# 3_6_2--esp32S3.net
KiCad netlist of a schematic drawn in EasyEDA Pro
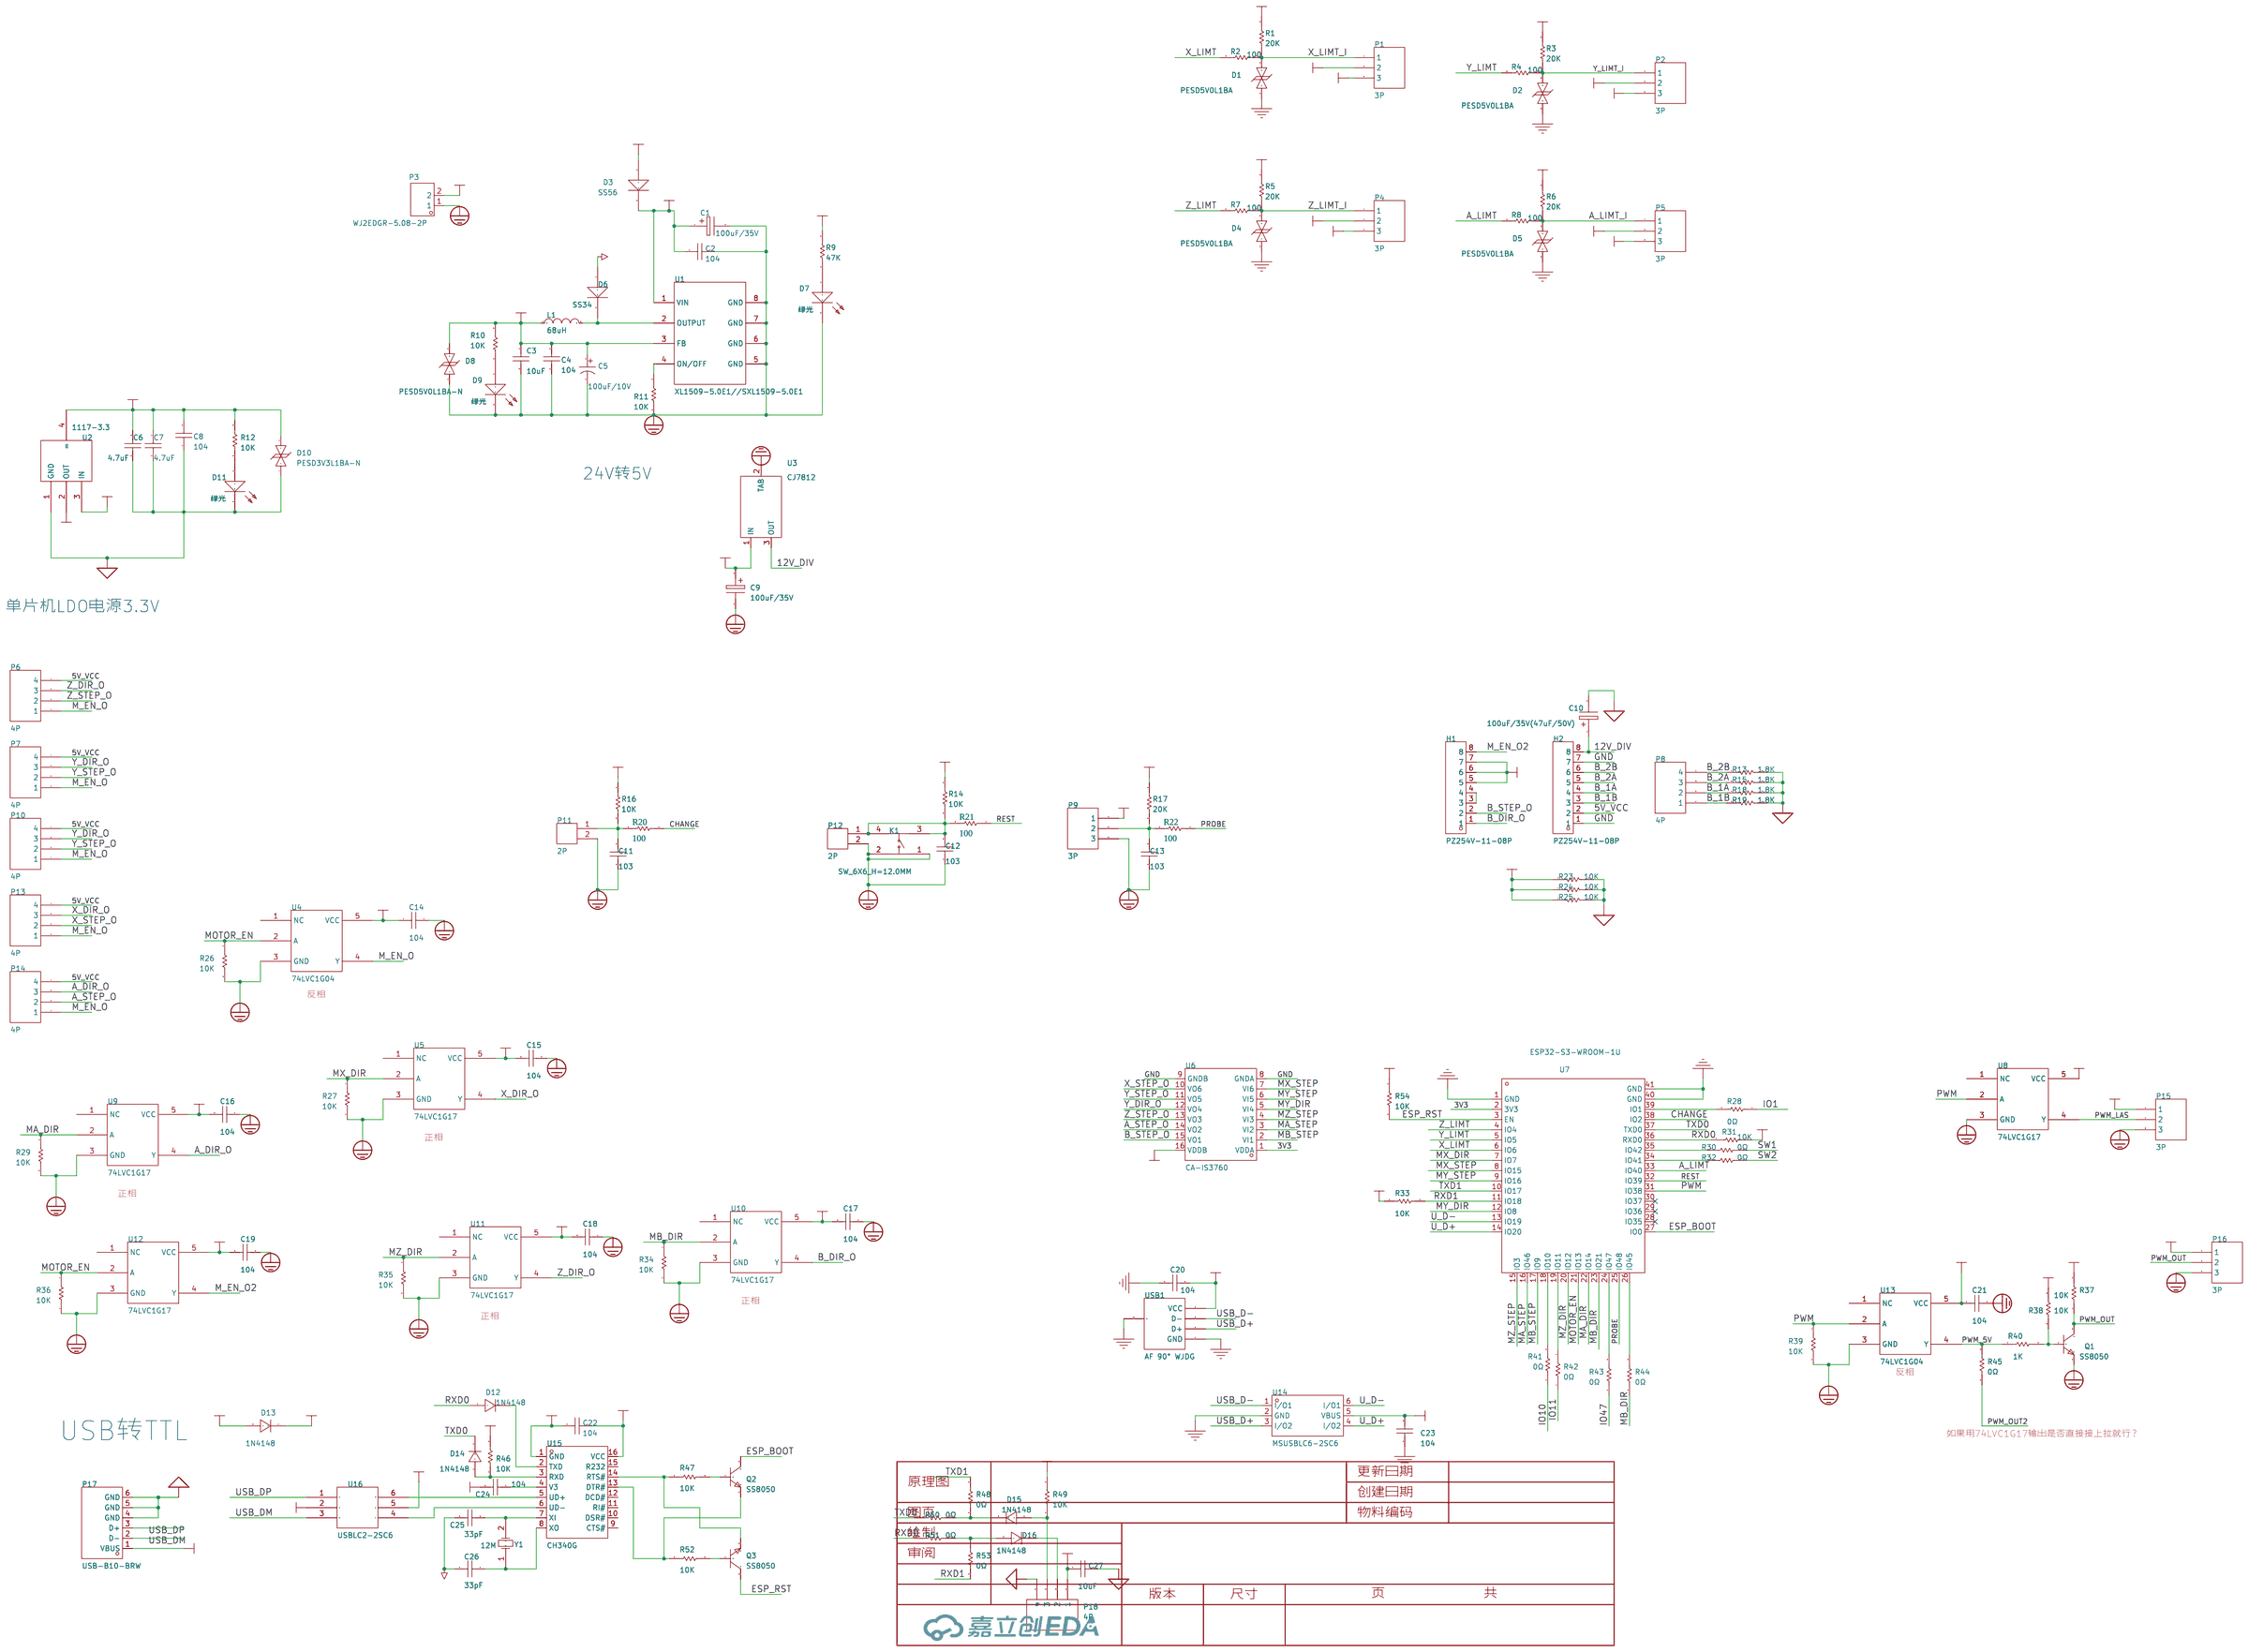
[diagram p0: schematic sheet]

(export (version "E")
  (design (tool "Eeschema 10.0.6"))
  (components
    (comp (ref "C1")
      (value "100uF/35V")
      (footprint "easyedapro:电解电容贴片10x10")
      (libsource (lib "easyedapro") (part "ELECTRO1"))
    )
    (comp (ref "C2")
      (value "104")
      (footprint "easyedapro:0603C")
      (description "Capacitor (Semiconductor SIM Model)")
      (libsource (lib "easyedapro") (part "Cap Semi"))
    )
    (comp (ref "C3") (value "10uF") (libsource (lib "") (part "CAP_1")))
    (comp (ref "C4")
      (value "104")
      (footprint "easyedapro:0603C")
      (description "Capacitor (Semiconductor SIM Model)")
      (libsource (lib "easyedapro") (part "Cap Semi"))
    )
    (comp (ref "C5")
      (value "100uF/10V")
      (footprint "easyedapro:CAP-SMD_BD5.0-L5.3-W5.3-RD")
      (fields (field (name "Manufacturer Part") "CS1A101M-CRD54") (field (name "Manufacturer") "ST(先科)"))
      (libsource (lib "easyedapro") (part "CS1A101M-CRD54"))
    )
    (comp (ref "C6") (value "4.7uF") (libsource (lib "") (part "CAP_1")))
    (comp (ref "C7") (value "4.7uF") (libsource (lib "") (part "CAP_1")))
    (comp (ref "C8")
      (value "104")
      (footprint "easyedapro:0603C")
      (description "Capacitor (Semiconductor SIM Model)")
      (libsource (lib "easyedapro") (part "Cap Semi"))
    )
    (comp (ref "C9")
      (value "100uF/35V")
      (footprint "easyedapro:电解电容贴片10x10")
      (libsource (lib "easyedapro") (part "ELECTRO1"))
    )
    (comp (ref "C10")
      (value "100uF/35V(47uF/50V)")
      (footprint "easyedapro:电解电容贴片10x10")
      (libsource (lib "easyedapro") (part "ELECTRO1"))
    )
    (comp (ref "C11") (value "103") (footprint "easyedapro:11") (libsource (lib "easyedapro") (part "CAP")))
    (comp (ref "C12") (value "103") (footprint "easyedapro:11") (libsource (lib "easyedapro") (part "CAP")))
    (comp (ref "C13") (value "103") (footprint "easyedapro:11") (libsource (lib "easyedapro") (part "CAP")))
    (comp (ref "C14")
      (value "104")
      (footprint "easyedapro:0603C")
      (description "Capacitor (Semiconductor SIM Model)")
      (libsource (lib "easyedapro") (part "Cap Semi"))
    )
    (comp (ref "C15")
      (value "104")
      (footprint "easyedapro:0603C")
      (description "Capacitor (Semiconductor SIM Model)")
      (libsource (lib "easyedapro") (part "Cap Semi"))
    )
    (comp (ref "C16")
      (value "104")
      (footprint "easyedapro:0603C")
      (description "Capacitor (Semiconductor SIM Model)")
      (libsource (lib "easyedapro") (part "Cap Semi"))
    )
    (comp (ref "C17")
      (value "104")
      (footprint "easyedapro:0603C")
      (description "Capacitor (Semiconductor SIM Model)")
      (libsource (lib "easyedapro") (part "Cap Semi"))
    )
    (comp (ref "C18")
      (value "104")
      (footprint "easyedapro:0603C")
      (description "Capacitor (Semiconductor SIM Model)")
      (libsource (lib "easyedapro") (part "Cap Semi"))
    )
    (comp (ref "C19")
      (value "104")
      (footprint "easyedapro:0603C")
      (description "Capacitor (Semiconductor SIM Model)")
      (libsource (lib "easyedapro") (part "Cap Semi"))
    )
    (comp (ref "C20")
      (value "104")
      (footprint "easyedapro:0603C")
      (description "Capacitor (Semiconductor SIM Model)")
      (libsource (lib "easyedapro") (part "Cap Semi"))
    )
    (comp (ref "C21")
      (value "104")
      (footprint "easyedapro:0603C")
      (description "Capacitor (Semiconductor SIM Model)")
      (libsource (lib "easyedapro") (part "Cap Semi"))
    )
    (comp (ref "C22")
      (value "104")
      (footprint "easyedapro:0603C")
      (description "Capacitor (Semiconductor SIM Model)")
      (libsource (lib "easyedapro") (part "Cap Semi"))
    )
    (comp (ref "C23")
      (value "104")
      (footprint "easyedapro:0603C")
      (description "Capacitor (Semiconductor SIM Model)")
      (libsource (lib "easyedapro") (part "Cap Semi"))
    )
    (comp (ref "C24")
      (value "104")
      (footprint "easyedapro:0603C")
      (description "Capacitor (Semiconductor SIM Model)")
      (libsource (lib "easyedapro") (part "Cap Semi"))
    )
    (comp (ref "C25")
      (value "18pF")
      (footprint "easyedapro:0603C")
      (description "Capacitor (Semiconductor SIM Model)")
      (libsource (lib "easyedapro") (part "Cap Semi"))
    )
    (comp (ref "C26")
      (value "18pF")
      (footprint "easyedapro:0603C")
      (description "Capacitor (Semiconductor SIM Model)")
      (libsource (lib "easyedapro") (part "Cap Semi"))
    )
    (comp (ref "C27") (value "10uF") (libsource (lib "") (part "CAP_1")))
    (comp (ref "D1")
      (value "PESD5V0L1BA")
      (footprint "easyedapro:SOD-523_L1.2-W0.8-LS1.6-BI")
      (description "极性:Bidirectional;反向关断电压（典型值）:5V (Max);击穿电压（最小值）:6V;箝位电压:15V;峰值脉冲电流（10/1000us）:5A (8/20us);")
      (fields (field (name "Manufacturer") "BORN伯恩半导体"))
      (libsource (lib "easyedapro") (part "PESD5V0S1BBN"))
    )
    (comp (ref "D2")
      (value "PESD5V0L1BA")
      (footprint "easyedapro:SOD-523_L1.2-W0.8-LS1.6-BI")
      (description "极性:Bidirectional;反向关断电压（典型值）:5V (Max);击穿电压（最小值）:6V;箝位电压:15V;峰值脉冲电流（10/1000us）:5A (8/20us);")
      (fields (field (name "Manufacturer") "BORN伯恩半导体"))
      (libsource (lib "easyedapro") (part "PESD5V0S1BBN"))
    )
    (comp (ref "D3") (value "SS56") (footprint "easyedapro:SMA") (libsource (lib "") (part "1N4148_1")))
    (comp (ref "D4")
      (value "PESD5V0L1BA")
      (footprint "easyedapro:SOD-523_L1.2-W0.8-LS1.6-BI")
      (description "极性:Bidirectional;反向关断电压（典型值）:5V (Max);击穿电压（最小值）:6V;箝位电压:15V;峰值脉冲电流（10/1000us）:5A (8/20us);")
      (fields (field (name "Manufacturer") "BORN伯恩半导体"))
      (libsource (lib "easyedapro") (part "PESD5V0S1BBN"))
    )
    (comp (ref "D5")
      (value "PESD5V0L1BA")
      (footprint "easyedapro:SOD-523_L1.2-W0.8-LS1.6-BI")
      (description "极性:Bidirectional;反向关断电压（典型值）:5V (Max);击穿电压（最小值）:6V;箝位电压:15V;峰值脉冲电流（10/1000us）:5A (8/20us);")
      (fields (field (name "Manufacturer") "BORN伯恩半导体"))
      (libsource (lib "easyedapro") (part "PESD5V0S1BBN"))
    )
    (comp (ref "D6") (value "SS34") (libsource (lib "easyedapro") (part "1N4148")))
    (comp (ref "D7")
      (value "绿光")
      (footprint "easyedapro:0603LED")
      (libsource (lib "easyedapro") (part "LED"))
    )
    (comp (ref "D8")
      (value "PESD5V0L1BA-N")
      (footprint "easyedapro:SOD-523_L1.2-W0.8-LS1.6-BI")
      (description "极性:Bidirectional;反向关断电压（典型值）:5V (Max);击穿电压（最小值）:6V;箝位电压:15V;峰值脉冲电流（10/1000us）:5A (8/20us);")
      (fields (field (name "Manufacturer") "BORN伯恩半导体"))
      (libsource (lib "easyedapro") (part "PESD5V0S1BBN"))
    )
    (comp (ref "D9")
      (value "绿光")
      (footprint "easyedapro:0603LED")
      (libsource (lib "easyedapro") (part "LED"))
    )
    (comp (ref "D10")
      (value "PESD3V3L1BA-N")
      (footprint "easyedapro:SOD-523_L1.2-W0.8-LS1.6-BI")
      (description "极性:Bidirectional;反向关断电压（典型值）:5V (Max);击穿电压（最小值）:6V;箝位电压:15V;峰值脉冲电流（10/1000us）:5A (8/20us);")
      (fields (field (name "Manufacturer") "BORN伯恩半导体"))
      (libsource (lib "easyedapro") (part "PESD5V0S1BBN"))
    )
    (comp (ref "D11")
      (value "绿光")
      (footprint "easyedapro:0603LED")
      (libsource (lib "easyedapro") (part "LED"))
    )
    (comp (ref "D12")
      (value "1N4148")
      (footprint "easyedapro:SOD-123_L2.8-W1.8-LS3.7-RD")
      (fields (field (name "Manufacturer") "MCC(美微科)"))
      (libsource (lib "easyedapro") (part "1N4148W-TP"))
    )
    (comp (ref "D13")
      (value "1N4148")
      (footprint "easyedapro:SOD-123_L2.8-W1.8-LS3.7-RD")
      (fields (field (name "Manufacturer") "MCC(美微科)"))
      (libsource (lib "easyedapro") (part "1N4148W-TP"))
    )
    (comp (ref "D14")
      (value "1N4148")
      (footprint "easyedapro:SOD-123_L2.8-W1.8-LS3.7-RD")
      (fields (field (name "Manufacturer") "MCC(美微科)"))
      (libsource (lib "easyedapro") (part "1N4148W-TP"))
    )
    (comp (ref "D15")
      (value "1N4148")
      (footprint "easyedapro:SOD-123_L2.8-W1.8-LS3.7-RD")
      (fields (field (name "Manufacturer") "MCC(美微科)"))
      (libsource (lib "easyedapro") (part "1N4148W-TP"))
    )
    (comp (ref "D16")
      (value "1N4148")
      (footprint "easyedapro:SOD-123_L2.8-W1.8-LS3.7-RD")
      (fields (field (name "Manufacturer") "MCC(美微科)"))
      (libsource (lib "easyedapro") (part "1N4148W-TP"))
    )
    (comp (ref "H1")
      (value "PZ254V-11-08P")
      (footprint "easyedapro:HDR-TH_8P-P2.54-V-M")
      (fields (field (name "Manufacturer") "XFCN(兴飞)"))
      (libsource (lib "easyedapro") (part "PZ254V-11-08P"))
    )
    (comp (ref "H2")
      (value "PZ254V-11-08P")
      (footprint "easyedapro:HDR-TH_8P-P2.54-V-M")
      (fields (field (name "Manufacturer") "XFCN(兴飞)"))
      (libsource (lib "easyedapro") (part "PZ254V-11-08P"))
    )
    (comp (ref "K1")
      (value "SW_6X6_H=12.0MM")
      (footprint "easyedapro:KEY-SMD_4P-L6.0-W6.0-P4.50-LS9.0")
      (libsource (lib "easyedapro") (part "SW_6X6_H=12.0MM"))
    )
    (comp (ref "L1")
      (value "68uH")
      (footprint "easyedapro:IND-SMD_L7.0-W7.0_SMDRI74-330MT")
      (description "电感值:33uH;精度:±20%;额定电流:960mA;饱和电流(Isat):1.8A;类型:屏蔽电感;")
      (fields (field (name "Manufacturer Part") "SMDRI74-330MT") (field (name "Manufacturer") "SXN(顺翔诺)"))
      (libsource (lib "easyedapro") (part "SMDRI74-330MT"))
    )
    (comp (ref "P1")
      (value "3P")
      (footprint "easyedapro:HDR1X3_CON")
      (libsource (lib "easyedapro") (part "3P"))
    )
    (comp (ref "P2")
      (value "3P")
      (footprint "easyedapro:HDR1X3_CON")
      (libsource (lib "easyedapro") (part "3P"))
    )
    (comp (ref "P3")
      (value "WJ2EDGR-5.08-2P")
      (footprint "easyedapro:CONN-TH_WJ2EDGR-5.08-2P")
      (description "每排PIN数:2;安装方式:弯针;排数:1;间距:5.08mm;连接器类型:板端/插座-开口;")
      (fields (field (name "Manufacturer") "KANGNEX(康奈克斯电气)"))
      (libsource (lib "easyedapro") (part "WJ2EDGR-5.08-2P"))
    )
    (comp (ref "P4")
      (value "3P")
      (footprint "easyedapro:HDR1X3_CON")
      (libsource (lib "easyedapro") (part "3P"))
    )
    (comp (ref "P5")
      (value "3P")
      (footprint "easyedapro:HDR1X3_CON")
      (libsource (lib "easyedapro") (part "3P"))
    )
    (comp (ref "P6")
      (value "4P")
      (footprint "easyedapro:HDR1X4_CON")
      (libsource (lib "easyedapro") (part "4P"))
    )
    (comp (ref "P7")
      (value "4P")
      (footprint "easyedapro:HDR1X4_CON")
      (libsource (lib "easyedapro") (part "4P"))
    )
    (comp (ref "P8")
      (value "4P")
      (footprint "easyedapro:HDR1X4_CON")
      (libsource (lib "easyedapro") (part "4P"))
    )
    (comp (ref "P9")
      (value "3P")
      (footprint "easyedapro:HDR1X3_CON")
      (libsource (lib "easyedapro") (part "3P"))
    )
    (comp (ref "P10")
      (value "4P")
      (footprint "easyedapro:HDR1X4_CON")
      (libsource (lib "easyedapro") (part "4P"))
    )
    (comp (ref "P11") (value "2P") (libsource (lib "easyedapro") (part "2P")))
    (comp (ref "P12") (value "2P") (libsource (lib "easyedapro") (part "2P")))
    (comp (ref "P13")
      (value "4P")
      (footprint "easyedapro:HDR1X4_CON")
      (libsource (lib "easyedapro") (part "4P"))
    )
    (comp (ref "P14")
      (value "4P")
      (footprint "easyedapro:HDR1X4_CON")
      (libsource (lib "easyedapro") (part "4P"))
    )
    (comp (ref "P15")
      (value "3P")
      (footprint "easyedapro:HDR1X3_CON")
      (libsource (lib "easyedapro") (part "3P"))
    )
    (comp (ref "P16")
      (value "3P")
      (footprint "easyedapro:HDR1X3_CON")
      (libsource (lib "easyedapro") (part "3P"))
    )
    (comp (ref "P17")
      (value "USB-B10-BRW")
      (footprint "easyedapro:USB-B-TH_USB-B10-BRW")
      (fields (field (name "Manufacturer") "XUNPU(讯普)"))
      (libsource (lib "easyedapro") (part "USB-B10-BRW"))
    )
    (comp (ref "P18")
      (value "4P")
      (footprint "easyedapro:HDR1X4_CON")
      (libsource (lib "easyedapro") (part "4P"))
    )
    (comp (ref "Q1")
      (value "SS8050")
      (footprint "easyedapro:SOT-23-3_L2.9-W1.3-P1.90-LS2.4-BR")
      (fields (field (name "Manufacturer") "CJ（江苏长电/长晶）"))
      (libsource (lib "easyedapro") (part "SS8050_C2150"))
    )
    (comp (ref "Q2")
      (value "SS8050")
      (footprint "easyedapro:SOT-23-3_L2.9-W1.3-P1.90-LS2.4-BR")
      (fields (field (name "Manufacturer") "Doeshare(德芯)"))
      (libsource (lib "easyedapro") (part "SS8050_C2931717"))
    )
    (comp (ref "Q3")
      (value "SS8050")
      (footprint "easyedapro:SOT-23-3_L2.9-W1.3-P1.90-LS2.4-BR")
      (fields (field (name "Manufacturer") "Doeshare(德芯)"))
      (libsource (lib "easyedapro") (part "SS8050_C2931717"))
    )
    (comp (ref "R1")
      (value "20K")
      (footprint "easyedapro:10")
      (description "Resistor")
      (libsource (lib "") (part "RES_1"))
    )
    (comp (ref "R2")
      (value "100")
      (footprint "easyedapro:10")
      (description "Resistor")
      (libsource (lib "") (part "RES_1"))
    )
    (comp (ref "R3")
      (value "20K")
      (footprint "easyedapro:10")
      (description "Resistor")
      (libsource (lib "") (part "RES_1"))
    )
    (comp (ref "R4")
      (value "100")
      (footprint "easyedapro:10")
      (description "Resistor")
      (libsource (lib "") (part "RES_1"))
    )
    (comp (ref "R5")
      (value "20K")
      (footprint "easyedapro:10")
      (description "Resistor")
      (libsource (lib "") (part "RES_1"))
    )
    (comp (ref "R6")
      (value "20K")
      (footprint "easyedapro:10")
      (description "Resistor")
      (libsource (lib "") (part "RES_1"))
    )
    (comp (ref "R7")
      (value "100")
      (footprint "easyedapro:10")
      (description "Resistor")
      (libsource (lib "") (part "RES_1"))
    )
    (comp (ref "R8")
      (value "100")
      (footprint "easyedapro:10")
      (description "Resistor")
      (libsource (lib "") (part "RES_1"))
    )
    (comp (ref "R9")
      (value "47K")
      (footprint "easyedapro:0603R")
      (description "Resistor")
      (libsource (lib "") (part "RES_1"))
    )
    (comp (ref "R10")
      (value "10K")
      (footprint "easyedapro:0603R")
      (description "Resistor")
      (libsource (lib "") (part "RES_1"))
    )
    (comp (ref "R11")
      (value "10K")
      (footprint "easyedapro:0603R")
      (description "Resistor")
      (libsource (lib "") (part "RES_1"))
    )
    (comp (ref "R12")
      (value "10K")
      (footprint "easyedapro:0603R")
      (description "Resistor")
      (libsource (lib "") (part "RES_1"))
    )
    (comp (ref "R13")
      (value "10K")
      (footprint "easyedapro:0603R")
      (description "Resistor")
      (libsource (lib "easyedapro") (part "10K"))
    )
    (comp (ref "R14")
      (value "10K")
      (footprint "easyedapro:0603R")
      (description "Resistor")
      (libsource (lib "") (part "RES_1"))
    )
    (comp (ref "R15")
      (value "10K")
      (footprint "easyedapro:0603R")
      (description "Resistor")
      (libsource (lib "easyedapro") (part "10K"))
    )
    (comp (ref "R16")
      (value "10K")
      (footprint "easyedapro:0603R")
      (description "Resistor")
      (libsource (lib "") (part "RES_1"))
    )
    (comp (ref "R17")
      (value "10K")
      (footprint "easyedapro:0603R")
      (description "Resistor")
      (libsource (lib "") (part "RES_1"))
    )
    (comp (ref "R18")
      (value "10K")
      (footprint "easyedapro:0603R")
      (description "Resistor")
      (libsource (lib "easyedapro") (part "10K"))
    )
    (comp (ref "R19")
      (value "10K")
      (footprint "easyedapro:0603R")
      (description "Resistor")
      (libsource (lib "easyedapro") (part "10K"))
    )
    (comp (ref "R20")
      (value "100")
      (description "Resistor")
      (fields (field (name "Publisher") "Altium Limited"))
      (libsource (lib "easyedapro") (part "RES"))
    )
    (comp (ref "R21")
      (value "100")
      (description "Resistor")
      (fields (field (name "Publisher") "Altium Limited"))
      (libsource (lib "easyedapro") (part "RES"))
    )
    (comp (ref "R22")
      (value "100")
      (description "Resistor")
      (fields (field (name "Publisher") "Altium Limited"))
      (libsource (lib "easyedapro") (part "RES"))
    )
    (comp (ref "R23")
      (value "10K")
      (footprint "easyedapro:0603R")
      (description "Resistor")
      (libsource (lib "easyedapro") (part "10K"))
    )
    (comp (ref "R24")
      (value "10K")
      (footprint "easyedapro:0603R")
      (description "Resistor")
      (libsource (lib "easyedapro") (part "10K"))
    )
    (comp (ref "R25")
      (value "10K")
      (footprint "easyedapro:0603R")
      (description "Resistor")
      (libsource (lib "easyedapro") (part "10K"))
    )
    (comp (ref "R26")
      (value "10K")
      (description "Resistor")
      (fields (field (name "Publisher") "Altium Limited"))
      (libsource (lib "easyedapro") (part "RES"))
    )
    (comp (ref "R27")
      (value "10K")
      (description "Resistor")
      (fields (field (name "Publisher") "Altium Limited"))
      (libsource (lib "easyedapro") (part "RES"))
    )
    (comp (ref "R28")
      (value "0Ω")
      (description "Resistor")
      (fields (field (name "Publisher") "Altium Limited"))
      (libsource (lib "easyedapro") (part "RES"))
    )
    (comp (ref "R29")
      (value "10K")
      (description "Resistor")
      (fields (field (name "Publisher") "Altium Limited"))
      (libsource (lib "easyedapro") (part "RES"))
    )
    (comp (ref "R30")
      (value "0Ω")
      (description "Resistor")
      (fields (field (name "Publisher") "Altium Limited"))
      (libsource (lib "easyedapro") (part "RES"))
    )
    (comp (ref "R31")
      (value "10K")
      (footprint "easyedapro:0603R")
      (description "Resistor")
      (libsource (lib "") (part "RES_1"))
    )
    (comp (ref "R32")
      (value "0Ω")
      (description "Resistor")
      (fields (field (name "Publisher") "Altium Limited"))
      (libsource (lib "easyedapro") (part "RES"))
    )
    (comp (ref "R33")
      (value "10K")
      (footprint "easyedapro:0603R")
      (description "Resistor")
      (libsource (lib "") (part "RES_1"))
    )
    (comp (ref "R34")
      (value "10K")
      (description "Resistor")
      (fields (field (name "Publisher") "Altium Limited"))
      (libsource (lib "easyedapro") (part "RES"))
    )
    (comp (ref "R35")
      (value "10K")
      (description "Resistor")
      (fields (field (name "Publisher") "Altium Limited"))
      (libsource (lib "easyedapro") (part "RES"))
    )
    (comp (ref "R36")
      (value "10K")
      (description "Resistor")
      (fields (field (name "Publisher") "Altium Limited"))
      (libsource (lib "easyedapro") (part "RES"))
    )
    (comp (ref "R37")
      (value "10K")
      (description "Resistor")
      (fields (field (name "Publisher") "Altium Limited"))
      (libsource (lib "easyedapro") (part "RES"))
    )
    (comp (ref "R38")
      (value "10K")
      (description "Resistor")
      (fields (field (name "Publisher") "Altium Limited"))
      (libsource (lib "easyedapro") (part "RES"))
    )
    (comp (ref "R39")
      (value "10K")
      (description "Resistor")
      (fields (field (name "Publisher") "Altium Limited"))
      (libsource (lib "easyedapro") (part "RES"))
    )
    (comp (ref "R40")
      (value "1K")
      (description "Resistor")
      (fields (field (name "Publisher") "Altium Limited"))
      (libsource (lib "easyedapro") (part "RES"))
    )
    (comp (ref "R41")
      (value "0Ω")
      (description "Resistor")
      (fields (field (name "Publisher") "Altium Limited"))
      (libsource (lib "easyedapro") (part "RES"))
    )
    (comp (ref "R42")
      (value "0Ω")
      (description "Resistor")
      (fields (field (name "Publisher") "Altium Limited"))
      (libsource (lib "easyedapro") (part "RES"))
    )
    (comp (ref "R43")
      (value "0Ω")
      (description "Resistor")
      (fields (field (name "Publisher") "Altium Limited"))
      (libsource (lib "easyedapro") (part "RES"))
    )
    (comp (ref "R44")
      (value "0Ω")
      (description "Resistor")
      (fields (field (name "Publisher") "Altium Limited"))
      (libsource (lib "easyedapro") (part "RES"))
    )
    (comp (ref "R45")
      (value "0Ω")
      (description "Resistor")
      (fields (field (name "Publisher") "Altium Limited"))
      (libsource (lib "easyedapro") (part "RES"))
    )
    (comp (ref "R46")
      (value "10K")
      (footprint "easyedapro:0603R")
      (description "Resistor")
      (libsource (lib "") (part "RES_1"))
    )
    (comp (ref "R47")
      (value "10K")
      (footprint "easyedapro:0603R")
      (description "Resistor")
      (libsource (lib "") (part "RES_1"))
    )
    (comp (ref "R48")
      (value "0Ω")
      (description "Resistor")
      (fields (field (name "Publisher") "Altium Limited"))
      (libsource (lib "easyedapro") (part "RES"))
    )
    (comp (ref "R49")
      (value "10K")
      (footprint "easyedapro:0603R")
      (description "Resistor")
      (libsource (lib "") (part "RES_1"))
    )
    (comp (ref "R50")
      (value "0Ω")
      (description "Resistor")
      (fields (field (name "Publisher") "Altium Limited"))
      (libsource (lib "easyedapro") (part "RES"))
    )
    (comp (ref "R51")
      (value "0Ω")
      (description "Resistor")
      (fields (field (name "Publisher") "Altium Limited"))
      (libsource (lib "easyedapro") (part "RES"))
    )
    (comp (ref "R52")
      (value "10K")
      (footprint "easyedapro:0603R")
      (description "Resistor")
      (libsource (lib "") (part "RES_1"))
    )
    (comp (ref "R53")
      (value "0Ω")
      (description "Resistor")
      (fields (field (name "Publisher") "Altium Limited"))
      (libsource (lib "easyedapro") (part "RES"))
    )
    (comp (ref "R54")
      (value "10K")
      (footprint "easyedapro:0603R")
      (description "Resistor")
      (libsource (lib "") (part "RES_1"))
    )
    (comp (ref "U1")
      (value "XL1509-5.0E1//SXL1509-5.0E1")
      (footprint "easyedapro:SOIC-8_L5.0-W4.0-P1.27-LS6.0-BL")
      (description "功能类型:降压型;同步整流:-;输出通道数:-;拓扑结构:-;输入电压:-;输出电流(最大值):-;开关频率:-;")
      (fields (field (name "Manufacturer") "XLSEMI(芯龙)"))
      (libsource (lib "easyedapro") (part "XL1509-5.0E1"))
    )
    (comp (ref "U2")
      (value "1117-3.3")
      (footprint "easyedapro:SOT-223")
      (libsource (lib "easyedapro") (part "LM1117"))
    )
    (comp (ref "U3")
      (value "CJ7812")
      (footprint "easyedapro:TO-263-2_L10.1-W9.1-P5.08-LS15.2-TL")
      (description "输出类型:固定;工作电压:35V;输出电压:12V;输出电流:1.5A;电源纹波抑制比(PSRR):71dB@(120Hz);输出极性:正极;")
      (fields (field (name "Manufacturer") "CJ(江苏长电/长晶)"))
      (libsource (lib "easyedapro") (part "CJ7812_C145151"))
    )
    (comp (ref "U4")
      (value "74LVC1G04")
      (footprint "easyedapro:SMD8")
      (libsource (lib "easyedapro") (part "74LVC1G04"))
    )
    (comp (ref "U5")
      (value "74LVC1G17")
      (footprint "easyedapro:SMD8")
      (libsource (lib "easyedapro") (part "74LVC1G04"))
    )
    (comp (ref "U6")
      (value "CA-IS3760")
      (footprint "easyedapro:SOIC-16_L9.9-W3.9-P1.27-LS6.0-BL")
      (fields (field (name "Manufacturer") "Chipanalog(川土微)"))
      (libsource (lib "easyedapro") (part "CA-IS3760HN"))
    )
    (comp (ref "U7")
      (value "ESP32-S3-WROOM-1U")
      (footprint "easyedapro:ESP32-S3-WROOM-1U")
      (fields
        (field (name "Manufacturer Part") "ESP32-S3-WROOM-1(N16R2)")
        (field (name "Manufacturer") "ESPRESSIF(----)")
      )
      (libsource (lib "easyedapro") (part "ESP32-S3-WROOM-1(N16R2)"))
    )
    (comp (ref "U8")
      (value "74LVC1G17")
      (footprint "easyedapro:SMD8")
      (libsource (lib "easyedapro") (part "74LVC1G04"))
    )
    (comp (ref "U9")
      (value "74LVC1G17")
      (footprint "easyedapro:SMD8")
      (libsource (lib "easyedapro") (part "74LVC1G04"))
    )
    (comp (ref "U10")
      (value "74LVC1G17")
      (footprint "easyedapro:SMD8")
      (libsource (lib "easyedapro") (part "74LVC1G04"))
    )
    (comp (ref "U11")
      (value "74LVC1G17")
      (footprint "easyedapro:SMD8")
      (libsource (lib "easyedapro") (part "74LVC1G04"))
    )
    (comp (ref "U12")
      (value "74LVC1G17")
      (footprint "easyedapro:SMD8")
      (libsource (lib "easyedapro") (part "74LVC1G04"))
    )
    (comp (ref "U13")
      (value "74LVC1G04")
      (footprint "easyedapro:SMD8")
      (libsource (lib "easyedapro") (part "74LVC1G04"))
    )
    (comp (ref "U14")
      (value "MSUSBLC6-2SC6")
      (footprint "easyedapro:SOT-23-6_L2.9-W1.6-P0.95-LS2.8-BL")
      (description "反向截止电压(Vrwm):5V;最大钳位电压:15V;峰值脉冲电流(Ipp)@10/1000us:6A;峰值脉冲功率(Ppp)@10/1000us:150W;击穿电压:9V;")
      (fields (field (name "Manufacturer") "MSKSEMI(美森科)"))
      (libsource (lib "easyedapro") (part "MSUSBLC6-2SC6"))
    )
    (comp (ref "U15")
      (value "CH340G")
      (footprint "easyedapro:SOIC-16_L9.9-W3.9-P1.27-LS6.0-BL")
      (description "应用功能:收发器;接口协议:USB 2.0;数据速率:2Mbps;")
      (fields (field (name "Manufacturer") "WCH(南京沁恒)"))
      (libsource (lib "easyedapro") (part "CH340G"))
    )
    (comp (ref "U16")
      (value "USBLC2-2SC6")
      (footprint "easyedapro:SOT-23-6")
      (libsource (lib "easyedapro") (part "DIP6"))
    )
    (comp (ref "USB1")
      (value "AF 90° WJDG")
      (footprint "easyedapro:USB-A-TH_AF-WJDG")
      (description "连接器类型:Type-A;标准:USB 2.0;公母:母;安装方式:弯插;触点数量:4P;端口数量:1;额定电流 - 电源:1.5A;工作温度范围:-25°C~+85°C;")
      (fields (field (name "Manufacturer") "SHOU HAN(首韩)"))
      (libsource (lib "easyedapro") (part "AF 90° WJDG"))
    )
    (comp (ref "Y1")
      (value "12M")
      (footprint "easyedapro:晶振贴片49SSMD")
      (description "Crystal Oscillator")
      (libsource (lib "easyedapro") (part "XTAL"))
    )
  )
  (nets
    (net (code "1") (name "/12V_DIV") (class "Default")
      (node (ref "C10") (pin "1") (pintype "unspecified"))
      (node (ref "H2") (pin "8") (pinfunction "8_8") (pintype "unspecified"))
      (node (ref "U3") (pin "3") (pinfunction "OUT_3") (pintype "unspecified"))
    )
    (net (code "2") (name "/A_DIR_O") (class "Default")
      (node (ref "P14") (pin "3") (pinfunction "3_3") (pintype "unspecified"))
      (node (ref "U9") (pin "4") (pinfunction "Y_4") (pintype "unspecified"))
    )
    (net (code "3") (name "/A_LIMT") (class "Default")
      (node (ref "R8") (pin "2") (pinfunction "2_2") (pintype "unspecified"))
      (node (ref "U7") (pin "33") (pinfunction "IO40_33") (pintype "unspecified"))
    )
    (net (code "4") (name "/A_LIMT_I") (class "Default")
      (node (ref "D5") (pin "2") (pinfunction "2_2") (pintype "input"))
      (node (ref "P5") (pin "1") (pinfunction "1_1") (pintype "unspecified"))
      (node (ref "R6") (pin "1") (pinfunction "1_1") (pintype "unspecified"))
      (node (ref "R8") (pin "1") (pinfunction "1_1") (pintype "unspecified"))
    )
    (net (code "5") (name "/A_STEP_O") (class "Default")
      (node (ref "P14") (pin "2") (pinfunction "2_2") (pintype "unspecified"))
      (node (ref "U6") (pin "14") (pinfunction "VO2_14") (pintype "unspecified"))
    )
    (net (code "6") (name "/B_1A") (class "Default")
      (node (ref "H2") (pin "4") (pinfunction "4_4") (pintype "unspecified"))
      (node (ref "P8") (pin "2") (pinfunction "2_2") (pintype "unspecified"))
      (node (ref "R18") (pin "1") (pinfunction "1_1") (pintype "unspecified"))
    )
    (net (code "7") (name "/B_1B") (class "Default")
      (node (ref "H2") (pin "3") (pinfunction "3_3") (pintype "unspecified"))
      (node (ref "P8") (pin "1") (pinfunction "1_1") (pintype "unspecified"))
      (node (ref "R19") (pin "1") (pinfunction "1_1") (pintype "unspecified"))
    )
    (net (code "8") (name "/B_2A") (class "Default")
      (node (ref "H2") (pin "5") (pinfunction "5_5") (pintype "unspecified"))
      (node (ref "P8") (pin "3") (pinfunction "3_3") (pintype "unspecified"))
      (node (ref "R15") (pin "1") (pinfunction "1_1") (pintype "unspecified"))
    )
    (net (code "9") (name "/B_2B") (class "Default")
      (node (ref "H2") (pin "6") (pinfunction "6_6") (pintype "unspecified"))
      (node (ref "P8") (pin "4") (pinfunction "4_4") (pintype "unspecified"))
      (node (ref "R13") (pin "1") (pinfunction "1_1") (pintype "unspecified"))
    )
    (net (code "10") (name "/B_DIR_O") (class "Default")
      (node (ref "H1") (pin "1") (pinfunction "1_1") (pintype "unspecified"))
      (node (ref "U10") (pin "4") (pinfunction "Y_4") (pintype "unspecified"))
    )
    (net (code "11") (name "/B_STEP_O") (class "Default")
      (node (ref "H1") (pin "2") (pinfunction "2_2") (pintype "unspecified"))
      (node (ref "U6") (pin "15") (pinfunction "VO1_15") (pintype "unspecified"))
    )
    (net (code "12") (name "/CHANGE") (class "Default")
      (node (ref "R20") (pin "1") (pinfunction "1_1") (pintype "input"))
      (node (ref "U7") (pin "38") (pinfunction "IO2_38") (pintype "unspecified"))
    )
    (net (code "13") (name "/ESP_BOOT") (class "Default")
      (node (ref "Q2") (pin "3") (pinfunction "C_3") (pintype "unspecified"))
      (node (ref "U7") (pin "27") (pinfunction "IO0_27") (pintype "unspecified"))
    )
    (net (code "14") (name "/ESP_RST") (class "Default")
      (node (ref "Q3") (pin "3") (pinfunction "C_3") (pintype "unspecified"))
      (node (ref "R54") (pin "2") (pinfunction "2_2") (pintype "unspecified"))
      (node (ref "U7") (pin "3") (pinfunction "EN_3") (pintype "unspecified"))
    )
    (net (code "15") (name "/IO1") (class "Default")
      (node (ref "R28") (pin "1") (pinfunction "1_1") (pintype "input"))
    )
    (net (code "16") (name "/IO10") (class "Default")
      (node (ref "R41") (pin "1") (pinfunction "1_1") (pintype "input"))
    )
    (net (code "17") (name "/IO11") (class "Default")
      (node (ref "R42") (pin "1") (pinfunction "1_1") (pintype "input"))
    )
    (net (code "18") (name "/IO47") (class "Default")
      (node (ref "R43") (pin "1") (pinfunction "1_1") (pintype "input"))
    )
    (net (code "19") (name "/MA_DIR") (class "Default")
      (node (ref "R29") (pin "1") (pinfunction "1_1") (pintype "input"))
      (node (ref "U7") (pin "22") (pinfunction "IO14_22") (pintype "unspecified"))
      (node (ref "U9") (pin "2") (pinfunction "A_2") (pintype "unspecified"))
    )
    (net (code "20") (name "/MA_STEP") (class "Default")
      (node (ref "U6") (pin "3") (pinfunction "VI2_3") (pintype "unspecified"))
      (node (ref "U7") (pin "16") (pinfunction "IO46_16") (pintype "unspecified"))
    )
    (net (code "21") (name "/MB_DIR") (class "Default")
      (node (ref "R34") (pin "1") (pinfunction "1_1") (pintype "input"))
      (node (ref "R44") (pin "1") (pinfunction "1_1") (pintype "input"))
      (node (ref "U10") (pin "2") (pinfunction "A_2") (pintype "unspecified"))
      (node (ref "U7") (pin "23") (pinfunction "IO21_23") (pintype "unspecified"))
    )
    (net (code "22") (name "/MB_STEP") (class "Default")
      (node (ref "U6") (pin "2") (pinfunction "VI1_2") (pintype "unspecified"))
      (node (ref "U7") (pin "17") (pinfunction "IO9_17") (pintype "unspecified"))
    )
    (net (code "23") (name "/MOTOR_EN") (class "Default")
      (node (ref "R26") (pin "1") (pinfunction "1_1") (pintype "input"))
      (node (ref "R36") (pin "1") (pinfunction "1_1") (pintype "input"))
      (node (ref "U12") (pin "2") (pinfunction "A_2") (pintype "unspecified"))
      (node (ref "U4") (pin "2") (pinfunction "A_2") (pintype "unspecified"))
      (node (ref "U7") (pin "21") (pinfunction "IO13_21") (pintype "unspecified"))
    )
    (net (code "24") (name "/MX_DIR") (class "Default")
      (node (ref "R27") (pin "1") (pinfunction "1_1") (pintype "input"))
      (node (ref "U5") (pin "2") (pinfunction "A_2") (pintype "unspecified"))
      (node (ref "U7") (pin "7") (pinfunction "IO7_7") (pintype "unspecified"))
    )
    (net (code "25") (name "/MX_STEP") (class "Default")
      (node (ref "U6") (pin "7") (pinfunction "VI6_7") (pintype "unspecified"))
      (node (ref "U7") (pin "8") (pinfunction "IO15_8") (pintype "unspecified"))
    )
    (net (code "26") (name "/MY_DIR") (class "Default")
      (node (ref "U6") (pin "5") (pinfunction "VI4_5") (pintype "unspecified"))
      (node (ref "U7") (pin "12") (pinfunction "IO8_12") (pintype "unspecified"))
    )
    (net (code "27") (name "/MY_STEP") (class "Default")
      (node (ref "U6") (pin "6") (pinfunction "VI5_6") (pintype "unspecified"))
      (node (ref "U7") (pin "9") (pinfunction "IO16_9") (pintype "unspecified"))
    )
    (net (code "28") (name "/MZ_DIR") (class "Default")
      (node (ref "R35") (pin "1") (pinfunction "1_1") (pintype "input"))
      (node (ref "U11") (pin "2") (pinfunction "A_2") (pintype "unspecified"))
      (node (ref "U7") (pin "20") (pinfunction "IO12_20") (pintype "unspecified"))
    )
    (net (code "29") (name "/MZ_STEP") (class "Default")
      (node (ref "U6") (pin "4") (pinfunction "VI3_4") (pintype "unspecified"))
      (node (ref "U7") (pin "15") (pinfunction "IO3_15") (pintype "unspecified"))
    )
    (net (code "30") (name "/M_EN_O") (class "Default")
      (node (ref "P10") (pin "1") (pinfunction "1_1") (pintype "unspecified"))
      (node (ref "P13") (pin "1") (pinfunction "1_1") (pintype "unspecified"))
      (node (ref "P14") (pin "1") (pinfunction "1_1") (pintype "unspecified"))
      (node (ref "P6") (pin "1") (pinfunction "1_1") (pintype "unspecified"))
      (node (ref "P7") (pin "1") (pinfunction "1_1") (pintype "unspecified"))
      (node (ref "U4") (pin "4") (pinfunction "Y_4") (pintype "unspecified"))
    )
    (net (code "31") (name "/M_EN_O2") (class "Default")
      (node (ref "H1") (pin "8") (pinfunction "8_8") (pintype "unspecified"))
      (node (ref "U12") (pin "4") (pinfunction "Y_4") (pintype "unspecified"))
    )
    (net (code "32") (name "/PROBE") (class "Default")
      (node (ref "R22") (pin "1") (pinfunction "1_1") (pintype "input"))
      (node (ref "U7") (pin "25") (pinfunction "IO48_25") (pintype "unspecified"))
    )
    (net (code "33") (name "/PWM") (class "Default")
      (node (ref "R39") (pin "1") (pinfunction "1_1") (pintype "input"))
      (node (ref "U13") (pin "2") (pinfunction "A_2") (pintype "unspecified"))
      (node (ref "U7") (pin "31") (pinfunction "IO38_31") (pintype "unspecified"))
      (node (ref "U8") (pin "2") (pinfunction "A_2") (pintype "unspecified"))
    )
    (net (code "34") (name "/PWM_5V") (class "Default")
      (node (ref "R40") (pin "1") (pinfunction "1_1") (pintype "input"))
      (node (ref "R45") (pin "2") (pinfunction "2_2") (pintype "input"))
      (node (ref "U13") (pin "4") (pinfunction "Y_4") (pintype "unspecified"))
    )
    (net (code "35") (name "/PWM_LAS") (class "Default")
      (node (ref "P15") (pin "2") (pinfunction "2_2") (pintype "unspecified"))
      (node (ref "U8") (pin "4") (pinfunction "Y_4") (pintype "unspecified"))
    )
    (net (code "36") (name "/PWM_OUT") (class "Default")
      (node (ref "P16") (pin "2") (pinfunction "2_2") (pintype "unspecified"))
      (node (ref "Q1") (pin "3") (pinfunction "C_3") (pintype "input"))
      (node (ref "R37") (pin "1") (pinfunction "1_1") (pintype "input"))
    )
    (net (code "37") (name "/PWM_OUT2") (class "Default")
      (node (ref "R45") (pin "1") (pinfunction "1_1") (pintype "input"))
    )
    (net (code "38") (name "/REST") (class "Default")
      (node (ref "R21") (pin "1") (pinfunction "1_1") (pintype "input"))
      (node (ref "U7") (pin "32") (pinfunction "IO39_32") (pintype "unspecified"))
    )
    (net (code "39") (name "/RXD0") (class "Default")
      (node (ref "D12") (pin "2") (pinfunction "A_2") (pintype "input"))
      (node (ref "R31") (pin "2") (pinfunction "2_2") (pintype "unspecified"))
      (node (ref "R51") (pin "1") (pinfunction "1_1") (pintype "input"))
      (node (ref "U7") (pin "36") (pinfunction "RXD0_36") (pintype "unspecified"))
    )
    (net (code "40") (name "/RXD1") (class "Default")
      (node (ref "R33") (pin "1") (pinfunction "1_1") (pintype "unspecified"))
      (node (ref "R53") (pin "1") (pinfunction "1_1") (pintype "input"))
      (node (ref "U7") (pin "11") (pinfunction "IO18_11") (pintype "unspecified"))
    )
    (net (code "41") (name "/SW1") (class "Default")
      (node (ref "R30") (pin "1") (pinfunction "1_1") (pintype "input"))
    )
    (net (code "42") (name "/SW2") (class "Default")
      (node (ref "R32") (pin "1") (pinfunction "1_1") (pintype "input"))
    )
    (net (code "43") (name "/TXD0") (class "Default")
      (node (ref "D14") (pin "1") (pinfunction "c_1") (pintype "input"))
      (node (ref "R50") (pin "1") (pinfunction "1_1") (pintype "input"))
      (node (ref "U7") (pin "37") (pinfunction "TXD0_37") (pintype "unspecified"))
    )
    (net (code "44") (name "/TXD1") (class "Default")
      (node (ref "R48") (pin "2") (pinfunction "2_2") (pintype "input"))
      (node (ref "U7") (pin "10") (pinfunction "IO17_10") (pintype "unspecified"))
    )
    (net (code "45") (name "/USB_D+") (class "Default")
      (node (ref "U14") (pin "3") (pinfunction "I/O2_3") (pintype "unspecified"))
      (node (ref "USB1") (pin "3") (pinfunction "D+_3") (pintype "input"))
    )
    (net (code "46") (name "/USB_D-") (class "Default")
      (node (ref "U14") (pin "1") (pinfunction "I/O1_1") (pintype "unspecified"))
      (node (ref "USB1") (pin "2") (pinfunction "D-_2") (pintype "input"))
    )
    (net (code "47") (name "/USB_DM") (class "Default")
      (node (ref "P17") (pin "2") (pinfunction "D-_2") (pintype "unspecified"))
      (node (ref "U16") (pin "3") (pinfunction "3_3") (pintype "unspecified"))
    )
    (net (code "48") (name "/USB_DP") (class "Default")
      (node (ref "P17") (pin "3") (pinfunction "D+_3") (pintype "unspecified"))
      (node (ref "U16") (pin "1") (pinfunction "1_1") (pintype "unspecified"))
    )
    (net (code "49") (name "/U_D+") (class "Default")
      (node (ref "U14") (pin "4") (pinfunction "I/O2_4") (pintype "unspecified"))
      (node (ref "U7") (pin "14") (pinfunction "IO20_14") (pintype "unspecified"))
    )
    (net (code "50") (name "/U_D-") (class "Default")
      (node (ref "U14") (pin "6") (pinfunction "I/O1_6") (pintype "unspecified"))
      (node (ref "U7") (pin "13") (pinfunction "IO19_13") (pintype "unspecified"))
    )
    (net (code "51") (name "/X_DIR_O") (class "Default")
      (node (ref "P13") (pin "3") (pinfunction "3_3") (pintype "unspecified"))
      (node (ref "U5") (pin "4") (pinfunction "Y_4") (pintype "unspecified"))
    )
    (net (code "52") (name "/X_LIMT") (class "Default")
      (node (ref "R2") (pin "2") (pinfunction "2_2") (pintype "unspecified"))
      (node (ref "U7") (pin "6") (pinfunction "IO6_6") (pintype "unspecified"))
    )
    (net (code "53") (name "/X_LIMT_I") (class "Default")
      (node (ref "D1") (pin "2") (pinfunction "2_2") (pintype "input"))
      (node (ref "P1") (pin "1") (pinfunction "1_1") (pintype "unspecified"))
      (node (ref "R1") (pin "1") (pinfunction "1_1") (pintype "unspecified"))
      (node (ref "R2") (pin "1") (pinfunction "1_1") (pintype "unspecified"))
    )
    (net (code "54") (name "/X_STEP_O") (class "Default")
      (node (ref "P13") (pin "2") (pinfunction "2_2") (pintype "unspecified"))
      (node (ref "U6") (pin "10") (pinfunction "VO6_10") (pintype "unspecified"))
    )
    (net (code "55") (name "/Y_DIR_O") (class "Default")
      (node (ref "P10") (pin "3") (pinfunction "3_3") (pintype "unspecified"))
      (node (ref "P7") (pin "3") (pinfunction "3_3") (pintype "unspecified"))
      (node (ref "U6") (pin "12") (pinfunction "VO4_12") (pintype "unspecified"))
    )
    (net (code "56") (name "/Y_LIMT") (class "Default")
      (node (ref "R4") (pin "2") (pinfunction "2_2") (pintype "unspecified"))
      (node (ref "U7") (pin "5") (pinfunction "IO5_5") (pintype "unspecified"))
    )
    (net (code "57") (name "/Y_LIMT_I") (class "Default")
      (node (ref "D2") (pin "2") (pinfunction "2_2") (pintype "input"))
      (node (ref "P2") (pin "1") (pinfunction "1_1") (pintype "unspecified"))
      (node (ref "R3") (pin "1") (pinfunction "1_1") (pintype "unspecified"))
      (node (ref "R4") (pin "1") (pinfunction "1_1") (pintype "unspecified"))
    )
    (net (code "58") (name "/Y_STEP_O") (class "Default")
      (node (ref "P10") (pin "2") (pinfunction "2_2") (pintype "unspecified"))
      (node (ref "P7") (pin "2") (pinfunction "2_2") (pintype "unspecified"))
      (node (ref "U6") (pin "11") (pinfunction "VO5_11") (pintype "unspecified"))
    )
    (net (code "59") (name "/Z_DIR_O") (class "Default")
      (node (ref "P6") (pin "3") (pinfunction "3_3") (pintype "unspecified"))
      (node (ref "U11") (pin "4") (pinfunction "Y_4") (pintype "unspecified"))
    )
    (net (code "60") (name "/Z_LIMT") (class "Default")
      (node (ref "R7") (pin "2") (pinfunction "2_2") (pintype "unspecified"))
      (node (ref "U7") (pin "4") (pinfunction "IO4_4") (pintype "unspecified"))
    )
    (net (code "61") (name "/Z_LIMT_I") (class "Default")
      (node (ref "D4") (pin "2") (pinfunction "2_2") (pintype "input"))
      (node (ref "P4") (pin "1") (pinfunction "1_1") (pintype "unspecified"))
      (node (ref "R5") (pin "1") (pinfunction "1_1") (pintype "unspecified"))
      (node (ref "R7") (pin "1") (pinfunction "1_1") (pintype "unspecified"))
    )
    (net (code "62") (name "/Z_STEP_O") (class "Default")
      (node (ref "P6") (pin "2") (pinfunction "2_2") (pintype "unspecified"))
      (node (ref "U6") (pin "13") (pinfunction "VO3_13") (pintype "unspecified"))
    )
    (net (code "63") (name "3V3") (class "Default")
      (node (ref "C6") (pin "2") (pinfunction "2_2") (pintype "input"))
      (node (ref "C7") (pin "2") (pinfunction "2_2") (pintype "input"))
      (node (ref "C8") (pin "2") (pinfunction "2_2") (pintype "unspecified"))
      (node (ref "D10") (pin "2") (pinfunction "2_2") (pintype "input"))
      (node (ref "R12") (pin "2") (pinfunction "2_2") (pintype "unspecified"))
      (node (ref "R14") (pin "1") (pinfunction "1_1") (pintype "unspecified"))
      (node (ref "R16") (pin "1") (pinfunction "1_1") (pintype "unspecified"))
      (node (ref "R31") (pin "1") (pinfunction "1_1") (pintype "unspecified"))
      (node (ref "R33") (pin "2") (pinfunction "2_2") (pintype "unspecified"))
      (node (ref "R54") (pin "1") (pinfunction "1_1") (pintype "unspecified"))
      (node (ref "U2") (pin "2") (pinfunction "OUT_2") (pintype "unspecified"))
      (node (ref "U2") (pin "4") (pinfunction "=_4") (pintype "unspecified"))
      (node (ref "U6") (pin "1") (pinfunction "VDDA_1") (pintype "unspecified"))
      (node (ref "U7") (pin "2") (pinfunction "3V3_2") (pintype "unspecified"))
    )
    (net (code "64") (name "5V_VCC") (class "Default")
      (node (ref "C14") (pin "2") (pinfunction "2_2") (pintype "unspecified"))
      (node (ref "C15") (pin "2") (pinfunction "2_2") (pintype "unspecified"))
      (node (ref "C16") (pin "2") (pinfunction "2_2") (pintype "unspecified"))
      (node (ref "C17") (pin "2") (pinfunction "2_2") (pintype "unspecified"))
      (node (ref "C18") (pin "2") (pinfunction "2_2") (pintype "unspecified"))
      (node (ref "C19") (pin "2") (pinfunction "2_2") (pintype "unspecified"))
      (node (ref "C20") (pin "1") (pinfunction "1_1") (pintype "unspecified"))
      (node (ref "C21") (pin "2") (pinfunction "2_2") (pintype "unspecified"))
      (node (ref "C22") (pin "1") (pinfunction "1_1") (pintype "unspecified"))
      (node (ref "C23") (pin "1") (pinfunction "1_1") (pintype "unspecified"))
      (node (ref "C27") (pin "1") (pinfunction "1_1") (pintype "input"))
      (node (ref "C3") (pin "1") (pinfunction "1_1") (pintype "input"))
      (node (ref "C4") (pin "2") (pinfunction "2_2") (pintype "unspecified"))
      (node (ref "C5") (pin "1") (pinfunction "1_1") (pintype "input"))
      (node (ref "D13") (pin "1") (pinfunction "c_1") (pintype "input"))
      (node (ref "D8") (pin "2") (pinfunction "2_2") (pintype "input"))
      (node (ref "H1") (pin "5") (pinfunction "5_5") (pintype "unspecified"))
      (node (ref "H1") (pin "6") (pinfunction "6_6") (pintype "unspecified"))
      (node (ref "H1") (pin "7") (pinfunction "7_7") (pintype "unspecified"))
      (node (ref "H2") (pin "2") (pinfunction "2_2") (pintype "unspecified"))
      (node (ref "L1") (pin "1") (pinfunction "1_1") (pintype "unspecified"))
      (node (ref "P1") (pin "3") (pinfunction "3_3") (pintype "unspecified"))
      (node (ref "P10") (pin "4") (pinfunction "4_4") (pintype "unspecified"))
      (node (ref "P13") (pin "4") (pinfunction "4_4") (pintype "unspecified"))
      (node (ref "P14") (pin "4") (pinfunction "4_4") (pintype "unspecified"))
      (node (ref "P16") (pin "1") (pinfunction "1_1") (pintype "unspecified"))
      (node (ref "P18") (pin "1") (pinfunction "1_1") (pintype "unspecified"))
      (node (ref "P2") (pin "3") (pinfunction "3_3") (pintype "unspecified"))
      (node (ref "P4") (pin "3") (pinfunction "3_3") (pintype "unspecified"))
      (node (ref "P5") (pin "3") (pinfunction "3_3") (pintype "unspecified"))
      (node (ref "P6") (pin "4") (pinfunction "4_4") (pintype "unspecified"))
      (node (ref "P7") (pin "4") (pinfunction "4_4") (pintype "unspecified"))
      (node (ref "P9") (pin "1") (pinfunction "1_1") (pintype "unspecified"))
      (node (ref "R1") (pin "2") (pinfunction "2_2") (pintype "unspecified"))
      (node (ref "R10") (pin "2") (pinfunction "2_2") (pintype "unspecified"))
      (node (ref "R17") (pin "1") (pinfunction "1_1") (pintype "unspecified"))
      (node (ref "R23") (pin "1") (pinfunction "1_1") (pintype "unspecified"))
      (node (ref "R24") (pin "1") (pinfunction "1_1") (pintype "unspecified"))
      (node (ref "R25") (pin "1") (pinfunction "1_1") (pintype "unspecified"))
      (node (ref "R3") (pin "2") (pinfunction "2_2") (pintype "unspecified"))
      (node (ref "R37") (pin "2") (pinfunction "2_2") (pintype "input"))
      (node (ref "R38") (pin "2") (pinfunction "2_2") (pintype "input"))
      (node (ref "R46") (pin "2") (pinfunction "2_2") (pintype "unspecified"))
      (node (ref "R49") (pin "2") (pinfunction "2_2") (pintype "unspecified"))
      (node (ref "R5") (pin "2") (pinfunction "2_2") (pintype "unspecified"))
      (node (ref "R6") (pin "2") (pinfunction "2_2") (pintype "unspecified"))
      (node (ref "U1") (pin "3") (pinfunction "FB_3") (pintype "input"))
      (node (ref "U10") (pin "5") (pinfunction "VCC_5") (pintype "unspecified"))
      (node (ref "U11") (pin "5") (pinfunction "VCC_5") (pintype "unspecified"))
      (node (ref "U12") (pin "5") (pinfunction "VCC_5") (pintype "unspecified"))
      (node (ref "U13") (pin "5") (pinfunction "VCC_5") (pintype "unspecified"))
      (node (ref "U14") (pin "5") (pinfunction "VBUS_5") (pintype "unspecified"))
      (node (ref "U15") (pin "16") (pinfunction "VCC_16") (pintype "unspecified"))
      (node (ref "U2") (pin "3") (pinfunction "IN_3") (pintype "unspecified"))
      (node (ref "U4") (pin "5") (pinfunction "VCC_5") (pintype "unspecified"))
      (node (ref "U5") (pin "5") (pinfunction "VCC_5") (pintype "unspecified"))
      (node (ref "U6") (pin "16") (pinfunction "VDDB_16") (pintype "unspecified"))
      (node (ref "U8") (pin "5") (pinfunction "VCC_5") (pintype "unspecified"))
      (node (ref "U9") (pin "5") (pinfunction "VCC_5") (pintype "unspecified"))
      (node (ref "USB1") (pin "1") (pinfunction "VCC_1") (pintype "input"))
    )
    (net (code "65") (name "24V") (class "Default")
      (node (ref "C9") (pin "1") (pintype "unspecified"))
      (node (ref "D3") (pin "1") (pinfunction "1_1") (pintype "unspecified"))
      (node (ref "P15") (pin "1") (pinfunction "1_1") (pintype "unspecified"))
      (node (ref "P3") (pin "2") (pinfunction "2_2") (pintype "input"))
      (node (ref "R9") (pin "2") (pinfunction "2_2") (pintype "unspecified"))
      (node (ref "U3") (pin "1") (pinfunction "IN_1") (pintype "unspecified"))
    )
    (net (code "66") (name "GND") (class "Default")
      (node (ref "C1") (pin "2") (pintype "unspecified"))
      (node (ref "C10") (pin "2") (pintype "unspecified"))
      (node (ref "C11") (pin "1") (pinfunction "1_1") (pintype "unspecified"))
      (node (ref "C12") (pin "1") (pinfunction "1_1") (pintype "unspecified"))
      (node (ref "C13") (pin "1") (pinfunction "1_1") (pintype "unspecified"))
      (node (ref "C14") (pin "1") (pinfunction "1_1") (pintype "unspecified"))
      (node (ref "C15") (pin "1") (pinfunction "1_1") (pintype "unspecified"))
      (node (ref "C16") (pin "1") (pinfunction "1_1") (pintype "unspecified"))
      (node (ref "C17") (pin "1") (pinfunction "1_1") (pintype "unspecified"))
      (node (ref "C18") (pin "1") (pinfunction "1_1") (pintype "unspecified"))
      (node (ref "C19") (pin "1") (pinfunction "1_1") (pintype "unspecified"))
      (node (ref "C2") (pin "1") (pinfunction "1_1") (pintype "unspecified"))
      (node (ref "C20") (pin "2") (pinfunction "2_2") (pintype "unspecified"))
      (node (ref "C21") (pin "1") (pinfunction "1_1") (pintype "unspecified"))
      (node (ref "C22") (pin "2") (pinfunction "2_2") (pintype "unspecified"))
      (node (ref "C23") (pin "2") (pinfunction "2_2") (pintype "unspecified"))
      (node (ref "C24") (pin "2") (pinfunction "2_2") (pintype "unspecified"))
      (node (ref "C25") (pin "2") (pinfunction "2_2") (pintype "unspecified"))
      (node (ref "C26") (pin "2") (pinfunction "2_2") (pintype "unspecified"))
      (node (ref "C27") (pin "2") (pinfunction "2_2") (pintype "input"))
      (node (ref "C3") (pin "2") (pinfunction "2_2") (pintype "input"))
      (node (ref "C4") (pin "1") (pinfunction "1_1") (pintype "unspecified"))
      (node (ref "C5") (pin "2") (pinfunction "2_2") (pintype "input"))
      (node (ref "C6") (pin "1") (pinfunction "1_1") (pintype "input"))
      (node (ref "C7") (pin "1") (pinfunction "1_1") (pintype "input"))
      (node (ref "C8") (pin "1") (pinfunction "1_1") (pintype "unspecified"))
      (node (ref "C9") (pin "2") (pintype "unspecified"))
      (node (ref "D1") (pin "1") (pinfunction "1_1") (pintype "input"))
      (node (ref "D10") (pin "1") (pinfunction "1_1") (pintype "input"))
      (node (ref "D11") (pin "2") (pinfunction "2_2") (pintype "unspecified"))
      (node (ref "D2") (pin "1") (pinfunction "1_1") (pintype "input"))
      (node (ref "D4") (pin "1") (pinfunction "1_1") (pintype "input"))
      (node (ref "D5") (pin "1") (pinfunction "1_1") (pintype "input"))
      (node (ref "D6") (pin "1") (pinfunction "1_1") (pintype "input"))
      (node (ref "D7") (pin "2") (pinfunction "2_2") (pintype "unspecified"))
      (node (ref "D8") (pin "1") (pinfunction "1_1") (pintype "input"))
      (node (ref "D9") (pin "2") (pinfunction "2_2") (pintype "unspecified"))
      (node (ref "H2") (pin "1") (pinfunction "1_1") (pintype "unspecified"))
      (node (ref "H2") (pin "7") (pinfunction "7_7") (pintype "unspecified"))
      (node (ref "K1") (pin "1") (pinfunction "1_1") (pintype "unspecified"))
      (node (ref "K1") (pin "2") (pinfunction "2_2") (pintype "unspecified"))
      (node (ref "P1") (pin "2") (pinfunction "2_2") (pintype "unspecified"))
      (node (ref "P11") (pin "2") (pintype "input"))
      (node (ref "P12") (pin "2") (pintype "input"))
      (node (ref "P15") (pin "3") (pinfunction "3_3") (pintype "unspecified"))
      (node (ref "P16") (pin "3") (pinfunction "3_3") (pintype "unspecified"))
      (node (ref "P17") (pin "4") (pinfunction "GND_4") (pintype "unspecified"))
      (node (ref "P17") (pin "5") (pinfunction "GND_5") (pintype "unspecified"))
      (node (ref "P17") (pin "6") (pinfunction "GND_6") (pintype "unspecified"))
      (node (ref "P18") (pin "4") (pinfunction "4_4") (pintype "unspecified"))
      (node (ref "P2") (pin "2") (pinfunction "2_2") (pintype "unspecified"))
      (node (ref "P3") (pin "1") (pinfunction "1_1") (pintype "input"))
      (node (ref "P4") (pin "2") (pinfunction "2_2") (pintype "unspecified"))
      (node (ref "P5") (pin "2") (pinfunction "2_2") (pintype "unspecified"))
      (node (ref "P9") (pin "3") (pinfunction "3_3") (pintype "unspecified"))
      (node (ref "Q1") (pin "2") (pinfunction "E_2") (pintype "input"))
      (node (ref "R11") (pin "2") (pinfunction "2_2") (pintype "unspecified"))
      (node (ref "R13") (pin "2") (pinfunction "2_2") (pintype "unspecified"))
      (node (ref "R15") (pin "2") (pinfunction "2_2") (pintype "unspecified"))
      (node (ref "R18") (pin "2") (pinfunction "2_2") (pintype "unspecified"))
      (node (ref "R19") (pin "2") (pinfunction "2_2") (pintype "unspecified"))
      (node (ref "R23") (pin "2") (pinfunction "2_2") (pintype "unspecified"))
      (node (ref "R24") (pin "2") (pinfunction "2_2") (pintype "unspecified"))
      (node (ref "R25") (pin "2") (pinfunction "2_2") (pintype "unspecified"))
      (node (ref "R26") (pin "2") (pinfunction "2_2") (pintype "input"))
      (node (ref "R27") (pin "2") (pinfunction "2_2") (pintype "input"))
      (node (ref "R29") (pin "2") (pinfunction "2_2") (pintype "input"))
      (node (ref "R34") (pin "2") (pinfunction "2_2") (pintype "input"))
      (node (ref "R35") (pin "2") (pinfunction "2_2") (pintype "input"))
      (node (ref "R36") (pin "2") (pinfunction "2_2") (pintype "input"))
      (node (ref "R39") (pin "2") (pinfunction "2_2") (pintype "input"))
      (node (ref "U1") (pin "5") (pinfunction "GND_5") (pintype "input"))
      (node (ref "U1") (pin "6") (pinfunction "GND_6") (pintype "input"))
      (node (ref "U1") (pin "7") (pinfunction "GND_7") (pintype "input"))
      (node (ref "U1") (pin "8") (pinfunction "GND_8") (pintype "input"))
      (node (ref "U10") (pin "3") (pinfunction "GND_3") (pintype "unspecified"))
      (node (ref "U11") (pin "3") (pinfunction "GND_3") (pintype "unspecified"))
      (node (ref "U12") (pin "3") (pinfunction "GND_3") (pintype "unspecified"))
      (node (ref "U13") (pin "3") (pinfunction "GND_3") (pintype "unspecified"))
      (node (ref "U14") (pin "2") (pinfunction "GND_2") (pintype "unspecified"))
      (node (ref "U15") (pin "1") (pinfunction "GND_1") (pintype "unspecified"))
      (node (ref "U16") (pin "2") (pinfunction "2_2") (pintype "unspecified"))
      (node (ref "U2") (pin "1") (pinfunction "GND_1") (pintype "unspecified"))
      (node (ref "U3") (pin "2") (pinfunction "TAB_2") (pintype "unspecified"))
      (node (ref "U4") (pin "3") (pinfunction "GND_3") (pintype "unspecified"))
      (node (ref "U5") (pin "3") (pinfunction "GND_3") (pintype "unspecified"))
      (node (ref "U6") (pin "8") (pinfunction "GNDA_8") (pintype "unspecified"))
      (node (ref "U6") (pin "9") (pinfunction "GNDB_9") (pintype "unspecified"))
      (node (ref "U7") (pin "1") (pinfunction "GND_1") (pintype "unspecified"))
      (node (ref "U7") (pin "40") (pinfunction "GND_40") (pintype "unspecified"))
      (node (ref "U7") (pin "41") (pinfunction "GND_41") (pintype "unspecified"))
      (node (ref "U8") (pin "3") (pinfunction "GND_3") (pintype "unspecified"))
      (node (ref "U9") (pin "3") (pinfunction "GND_3") (pintype "unspecified"))
      (node (ref "USB1") (pin "4") (pinfunction "GND_4") (pintype "input"))
      (node (ref "USB1") (pin "5") (pinfunction "SHLD_5") (pintype "unspecified"))
    )
    (net (code "67") (name "Net-(C11-Pad2)") (class "Default")
      (node (ref "C11") (pin "2") (pinfunction "2_2") (pintype "unspecified"))
      (node (ref "P11") (pin "1") (pintype "input"))
      (node (ref "R16") (pin "2") (pinfunction "2_2") (pintype "unspecified"))
      (node (ref "R20") (pin "2") (pinfunction "2_2") (pintype "input"))
    )
    (net (code "68") (name "Net-(C12-Pad2)") (class "Default")
      (node (ref "C12") (pin "2") (pinfunction "2_2") (pintype "unspecified"))
      (node (ref "K1") (pin "3") (pinfunction "3_3") (pintype "unspecified"))
      (node (ref "K1") (pin "4") (pinfunction "4_4") (pintype "unspecified"))
      (node (ref "P12") (pin "1") (pintype "input"))
      (node (ref "R14") (pin "2") (pinfunction "2_2") (pintype "unspecified"))
      (node (ref "R21") (pin "2") (pinfunction "2_2") (pintype "input"))
    )
    (net (code "69") (name "Net-(C13-Pad2)") (class "Default")
      (node (ref "C13") (pin "2") (pinfunction "2_2") (pintype "unspecified"))
      (node (ref "P9") (pin "2") (pinfunction "2_2") (pintype "unspecified"))
      (node (ref "R17") (pin "2") (pinfunction "2_2") (pintype "unspecified"))
      (node (ref "R22") (pin "2") (pinfunction "2_2") (pintype "input"))
    )
    (net (code "70") (name "Net-(D7-Pad1)") (class "Default")
      (node (ref "D7") (pin "1") (pinfunction "1_1") (pintype "unspecified"))
      (node (ref "R9") (pin "1") (pinfunction "1_1") (pintype "unspecified"))
    )
    (net (code "71") (name "Net-(D9-Pad1)") (class "Default")
      (node (ref "D9") (pin "1") (pinfunction "1_1") (pintype "unspecified"))
      (node (ref "R10") (pin "1") (pinfunction "1_1") (pintype "unspecified"))
    )
    (net (code "72") (name "Net-(D11-Pad1)") (class "Default")
      (node (ref "D11") (pin "1") (pinfunction "1_1") (pintype "unspecified"))
      (node (ref "R12") (pin "1") (pinfunction "1_1") (pintype "unspecified"))
    )
    (net (code "73") (name "Net-(D12-c)") (class "Default")
      (node (ref "D12") (pin "1") (pinfunction "c_1") (pintype "input"))
      (node (ref "U15") (pin "2") (pinfunction "TXD_2") (pintype "unspecified"))
    )
    (net (code "74") (name "Net-(D14-A)") (class "Default")
      (node (ref "D14") (pin "2") (pinfunction "A_2") (pintype "input"))
      (node (ref "R46") (pin "1") (pinfunction "1_1") (pintype "unspecified"))
      (node (ref "U15") (pin "3") (pinfunction "RXD_3") (pintype "unspecified"))
    )
    (net (code "75") (name "Net-(D15-A)") (class "Default")
      (node (ref "D15") (pin "2") (pinfunction "A_2") (pintype "input"))
      (node (ref "P18") (pin "3") (pinfunction "3_3") (pintype "unspecified"))
      (node (ref "R49") (pin "1") (pinfunction "1_1") (pintype "unspecified"))
    )
    (net (code "76") (name "Net-(D15-c)") (class "Default")
      (node (ref "D15") (pin "1") (pinfunction "c_1") (pintype "input"))
      (node (ref "R48") (pin "1") (pinfunction "1_1") (pintype "input"))
      (node (ref "R50") (pin "2") (pinfunction "2_2") (pintype "input"))
    )
    (net (code "77") (name "Net-(D16-A)") (class "Default")
      (node (ref "D16") (pin "2") (pinfunction "A_2") (pintype "input"))
      (node (ref "R51") (pin "2") (pinfunction "2_2") (pintype "input"))
      (node (ref "R53") (pin "2") (pinfunction "2_2") (pintype "input"))
    )
    (net (code "78") (name "Net-(D16-c)") (class "Default")
      (node (ref "D16") (pin "1") (pinfunction "c_1") (pintype "input"))
      (node (ref "P18") (pin "2") (pinfunction "2_2") (pintype "unspecified"))
    )
    (net (code "79") (name "Net-(H1-Pad3)") (class "Default")
      (node (ref "H1") (pin "3") (pinfunction "3_3") (pintype "unspecified"))
      (node (ref "H1") (pin "4") (pinfunction "4_4") (pintype "unspecified"))
    )
    (net (code "80") (name "Net-(Q1-B)") (class "Default")
      (node (ref "Q1") (pin "1") (pinfunction "B_1") (pintype "input"))
      (node (ref "R38") (pin "1") (pinfunction "1_1") (pintype "input"))
      (node (ref "R40") (pin "2") (pinfunction "2_2") (pintype "input"))
    )
    (net (code "81") (name "Net-(Q2-B)") (class "Default")
      (node (ref "Q2") (pin "1") (pinfunction "B_1") (pintype "unspecified"))
      (node (ref "R47") (pin "2") (pinfunction "2_2") (pintype "unspecified"))
    )
    (net (code "82") (name "Net-(Q2-E)") (class "Default")
      (node (ref "Q2") (pin "2") (pinfunction "E_2") (pintype "unspecified"))
      (node (ref "R52") (pin "1") (pinfunction "1_1") (pintype "unspecified"))
      (node (ref "U15") (pin "13") (pinfunction "DTR#_13") (pintype "unspecified"))
    )
    (net (code "83") (name "Net-(Q3-B)") (class "Default")
      (node (ref "Q3") (pin "1") (pinfunction "B_1") (pintype "unspecified"))
      (node (ref "R52") (pin "2") (pinfunction "2_2") (pintype "unspecified"))
    )
    (net (code "84") (name "Net-(Q3-E)") (class "Default")
      (node (ref "Q3") (pin "2") (pinfunction "E_2") (pintype "unspecified"))
      (node (ref "R47") (pin "1") (pinfunction "1_1") (pintype "unspecified"))
      (node (ref "U15") (pin "14") (pinfunction "RTS#_14") (pintype "unspecified"))
    )
    (net (code "85") (name "Net-(U1-ON{slash}OFF)") (class "Default")
      (node (ref "R11") (pin "1") (pinfunction "1_1") (pintype "unspecified"))
      (node (ref "U1") (pin "4") (pinfunction "ON/OFF_4") (pintype "input"))
    )
    (net (code "86") (name "Net-(U1-OUTPUT)") (class "Default")
      (node (ref "D6") (pin "2") (pinfunction "2_2") (pintype "input"))
      (node (ref "L1") (pin "2") (pinfunction "2_2") (pintype "unspecified"))
      (node (ref "U1") (pin "2") (pinfunction "OUTPUT_2") (pintype "input"))
    )
    (net (code "87") (name "Net-(U7-IO1)") (class "Default")
      (node (ref "R28") (pin "2") (pinfunction "2_2") (pintype "input"))
      (node (ref "U7") (pin "39") (pinfunction "IO1_39") (pintype "unspecified"))
    )
    (net (code "88") (name "Net-(U7-IO10)") (class "Default")
      (node (ref "R41") (pin "2") (pinfunction "2_2") (pintype "input"))
      (node (ref "U7") (pin "18") (pinfunction "IO10_18") (pintype "unspecified"))
    )
    (net (code "89") (name "Net-(U7-IO11)") (class "Default")
      (node (ref "R42") (pin "2") (pinfunction "2_2") (pintype "input"))
      (node (ref "U7") (pin "19") (pinfunction "IO11_19") (pintype "unspecified"))
    )
    (net (code "90") (name "Net-(U7-IO41)") (class "Default")
      (node (ref "R32") (pin "2") (pinfunction "2_2") (pintype "input"))
      (node (ref "U7") (pin "34") (pinfunction "IO41_34") (pintype "unspecified"))
    )
    (net (code "91") (name "Net-(U7-IO42)") (class "Default")
      (node (ref "R30") (pin "2") (pinfunction "2_2") (pintype "input"))
      (node (ref "U7") (pin "35") (pinfunction "IO42_35") (pintype "unspecified"))
    )
    (net (code "92") (name "Net-(U7-IO45)") (class "Default")
      (node (ref "R44") (pin "2") (pinfunction "2_2") (pintype "input"))
      (node (ref "U7") (pin "26") (pinfunction "IO45_26") (pintype "unspecified"))
    )
    (net (code "93") (name "Net-(U7-IO47)") (class "Default")
      (node (ref "R43") (pin "2") (pinfunction "2_2") (pintype "input"))
      (node (ref "U7") (pin "24") (pinfunction "IO47_24") (pintype "unspecified"))
    )
    (net (code "94") (name "Net-(U15-UD+)") (class "Default")
      (node (ref "U15") (pin "5") (pinfunction "UD+_5") (pintype "unspecified"))
      (node (ref "U16") (pin "6") (pinfunction "6_6") (pintype "unspecified"))
    )
    (net (code "95") (name "Net-(U15-UD-)") (class "Default")
      (node (ref "U15") (pin "6") (pinfunction "UD-_6") (pintype "unspecified"))
      (node (ref "U16") (pin "4") (pinfunction "4_4") (pintype "unspecified"))
    )
    (net (code "96") (name "Net-(U15-V3)") (class "Default")
      (node (ref "C24") (pin "1") (pinfunction "1_1") (pintype "unspecified"))
      (node (ref "U15") (pin "4") (pinfunction "V3_4") (pintype "unspecified"))
    )
    (net (code "97") (name "Net-(U15-XI)") (class "Default")
      (node (ref "C25") (pin "1") (pinfunction "1_1") (pintype "unspecified"))
      (node (ref "U15") (pin "7") (pinfunction "XI_7") (pintype "unspecified"))
      (node (ref "Y1") (pin "2") (pinfunction "OSC2_2") (pintype "unspecified"))
    )
    (net (code "98") (name "Net-(U15-XO)") (class "Default")
      (node (ref "C26") (pin "1") (pinfunction "1_1") (pintype "unspecified"))
      (node (ref "U15") (pin "8") (pinfunction "XO_8") (pintype "unspecified"))
      (node (ref "Y1") (pin "1") (pinfunction "OSC1_1") (pintype "unspecified"))
    )
    (net (code "99") (name "VIN_24V") (class "Default")
      (node (ref "C1") (pin "1") (pintype "unspecified"))
      (node (ref "C2") (pin "2") (pinfunction "2_2") (pintype "unspecified"))
      (node (ref "D3") (pin "2") (pinfunction "2_2") (pintype "unspecified"))
      (node (ref "U1") (pin "1") (pinfunction "VIN_1") (pintype "input"))
    )
    (net (code "100") (name "VUSB") (class "Default")
      (node (ref "D13") (pin "2") (pinfunction "A_2") (pintype "input"))
      (node (ref "P17") (pin "1") (pinfunction "VBUS_1") (pintype "unspecified"))
      (node (ref "U16") (pin "5") (pinfunction "5_5") (pintype "unspecified"))
    )
    (net (code "101") (name "unconnected-(U4-NC-Pad1)") (class "Default")
      (node (ref "U4") (pin "1") (pinfunction "NC_1") (pintype "unspecified"))
    )
    (net (code "102") (name "unconnected-(U5-NC-Pad1)") (class "Default")
      (node (ref "U5") (pin "1") (pinfunction "NC_1") (pintype "unspecified"))
    )
    (net (code "103") (name "unconnected-(U7-IO35-Pad28)") (class "Default")
      (node (ref "U7") (pin "28") (pinfunction "IO35_28") (pintype "unspecified+no_connect"))
    )
    (net (code "104") (name "unconnected-(U7-IO36-Pad29)") (class "Default")
      (node (ref "U7") (pin "29") (pinfunction "IO36_29") (pintype "unspecified+no_connect"))
    )
    (net (code "105") (name "unconnected-(U7-IO37-Pad30)") (class "Default")
      (node (ref "U7") (pin "30") (pinfunction "IO37_30") (pintype "unspecified+no_connect"))
    )
    (net (code "106") (name "unconnected-(U8-NC-Pad1)") (class "Default")
      (node (ref "U8") (pin "1") (pinfunction "NC_1") (pintype "unspecified"))
    )
    (net (code "107") (name "unconnected-(U9-NC-Pad1)") (class "Default")
      (node (ref "U9") (pin "1") (pinfunction "NC_1") (pintype "unspecified"))
    )
    (net (code "108") (name "unconnected-(U10-NC-Pad1)") (class "Default")
      (node (ref "U10") (pin "1") (pinfunction "NC_1") (pintype "unspecified"))
    )
    (net (code "109") (name "unconnected-(U11-NC-Pad1)") (class "Default")
      (node (ref "U11") (pin "1") (pinfunction "NC_1") (pintype "unspecified"))
    )
    (net (code "110") (name "unconnected-(U12-NC-Pad1)") (class "Default")
      (node (ref "U12") (pin "1") (pinfunction "NC_1") (pintype "unspecified"))
    )
    (net (code "111") (name "unconnected-(U13-NC-Pad1)") (class "Default")
      (node (ref "U13") (pin "1") (pinfunction "NC_1") (pintype "unspecified"))
    )
    (net (code "112") (name "unconnected-(U15-CTS#-Pad9)") (class "Default")
      (node (ref "U15") (pin "9") (pinfunction "CTS#_9") (pintype "unspecified"))
    )
    (net (code "113") (name "unconnected-(U15-DCD#-Pad12)") (class "Default")
      (node (ref "U15") (pin "12") (pinfunction "DCD#_12") (pintype "unspecified"))
    )
    (net (code "114") (name "unconnected-(U15-DSR#-Pad10)") (class "Default")
      (node (ref "U15") (pin "10") (pinfunction "DSR#_10") (pintype "unspecified"))
    )
    (net (code "115") (name "unconnected-(U15-R232-Pad15)") (class "Default")
      (node (ref "U15") (pin "15") (pinfunction "R232_15") (pintype "unspecified"))
    )
    (net (code "116") (name "unconnected-(U15-RI#-Pad11)") (class "Default")
      (node (ref "U15") (pin "11") (pinfunction "RI#_11") (pintype "unspecified"))
    )
  )
)
